# pwm-fan-controller.net
KiCad netlist of a schematic drawn in EAGLE
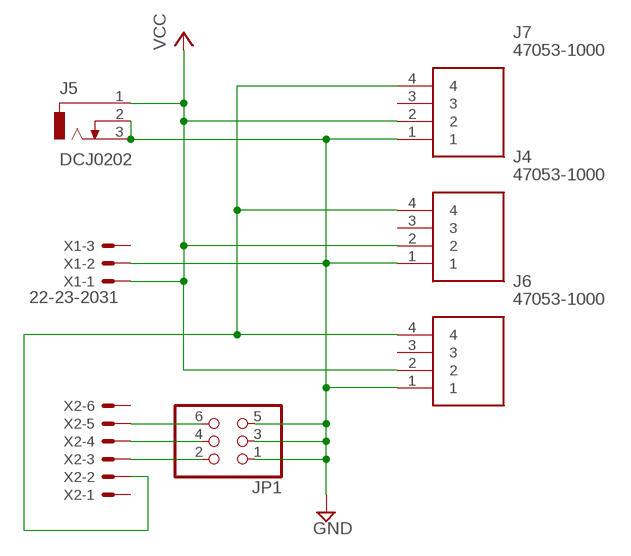
[diagram p0: schematic, sheet 1]

(export (version "E")
  (design (tool "Eeschema 10.0.6"))
  (components
    (comp (ref "J4")
      (value "47053-1000")
      (footprint "eagle-import:470531000")
      (fields (field (name "MF") "Molex"))
      (libsource (lib "eagle-import") (part "47053-1000"))
    )
    (comp (ref "J5")
      (value "DCJ0202")
      (footprint "eagle-import:DCJ0202")
      (libsource (lib "eagle-import") (part "DCJ0202"))
    )
    (comp (ref "J6")
      (value "47053-1000")
      (footprint "eagle-import:470531000")
      (fields (field (name "MF") "Molex"))
      (libsource (lib "eagle-import") (part "47053-1000"))
    )
    (comp (ref "J7")
      (value "47053-1000")
      (footprint "eagle-import:470531000")
      (fields (field (name "MF") "Molex"))
      (libsource (lib "eagle-import") (part "47053-1000"))
    )
    (comp (ref "JP1")
      (value "PINHD-2X3")
      (footprint "eagle-import:2X03")
      (libsource (lib "eagle-import") (part "PINHD-2X3"))
    )
    (comp (ref "X1")
      (value "22-23-2031")
      (footprint "eagle-import:22-23-2031")
      (fields (field (name "MF") "MOLEX"))
      (libsource (lib "eagle-import") (part "22-23-2031"))
    )
    (comp (ref "X2")
      (value "22-23-2061")
      (footprint "eagle-import:22-23-2061")
      (fields (field (name "MF") "MOLEX"))
      (libsource (lib "eagle-import") (part "22-23-2061"))
    )
  )
  (nets
    (net (code "1") (name "GND") (class "Default")
      (node (ref "J4") (pin "1") (pinfunction "1_1") (pintype "bidirectional"))
      (node (ref "J5") (pin "2") (pinfunction "2_2") (pintype "passive"))
      (node (ref "J5") (pin "3") (pinfunction "3_3") (pintype "passive"))
      (node (ref "J6") (pin "1") (pinfunction "1_1") (pintype "bidirectional"))
      (node (ref "J7") (pin "1") (pinfunction "1_1") (pintype "bidirectional"))
      (node (ref "JP1") (pin "1") (pinfunction "1_1") (pintype "passive"))
      (node (ref "JP1") (pin "3") (pinfunction "3_3") (pintype "passive"))
      (node (ref "JP1") (pin "5") (pinfunction "5_5") (pintype "passive"))
      (node (ref "X1") (pin "2") (pinfunction "S_2") (pintype "passive"))
    )
    (net (code "2") (name "Net-(X2B-S)") (class "Default")
      (node (ref "J4") (pin "4") (pinfunction "4_4") (pintype "bidirectional"))
      (node (ref "J6") (pin "4") (pinfunction "4_4") (pintype "bidirectional"))
      (node (ref "J7") (pin "4") (pinfunction "4_4") (pintype "bidirectional"))
      (node (ref "X2") (pin "2") (pinfunction "S_2") (pintype "passive"))
    )
    (net (code "3") (name "Net-(X2C-S)") (class "Default")
      (node (ref "JP1") (pin "2") (pinfunction "2_2") (pintype "passive"))
      (node (ref "X2") (pin "3") (pinfunction "S_3") (pintype "passive"))
    )
    (net (code "4") (name "Net-(X2D-S)") (class "Default")
      (node (ref "JP1") (pin "4") (pinfunction "4_4") (pintype "passive"))
      (node (ref "X2") (pin "4") (pinfunction "S_4") (pintype "passive"))
    )
    (net (code "5") (name "Net-(X2E-S)") (class "Default")
      (node (ref "JP1") (pin "6") (pinfunction "6_6") (pintype "passive"))
      (node (ref "X2") (pin "5") (pinfunction "S_5") (pintype "passive"))
    )
    (net (code "6") (name "VCC") (class "Default")
      (node (ref "J4") (pin "2") (pinfunction "2_2") (pintype "bidirectional"))
      (node (ref "J5") (pin "1") (pinfunction "1_1") (pintype "passive"))
      (node (ref "J6") (pin "2") (pinfunction "2_2") (pintype "bidirectional"))
      (node (ref "J7") (pin "2") (pinfunction "2_2") (pintype "bidirectional"))
      (node (ref "X1") (pin "1") (pinfunction "S_1") (pintype "passive"))
    )
    (net (code "7") (name "unconnected-(J4-Pad3)") (class "Default")
      (node (ref "J4") (pin "3") (pinfunction "3_3") (pintype "bidirectional"))
    )
    (net (code "8") (name "unconnected-(J6-Pad3)") (class "Default")
      (node (ref "J6") (pin "3") (pinfunction "3_3") (pintype "bidirectional"))
    )
    (net (code "9") (name "unconnected-(J7-Pad3)") (class "Default")
      (node (ref "J7") (pin "3") (pinfunction "3_3") (pintype "bidirectional"))
    )
    (net (code "10") (name "unconnected-(X1C-S-Pad3)") (class "Default")
      (node (ref "X1") (pin "3") (pinfunction "S_3") (pintype "passive"))
    )
    (net (code "11") (name "unconnected-(X2A-S-Pad1)") (class "Default")
      (node (ref "X2") (pin "1") (pinfunction "S_1") (pintype "passive"))
    )
    (net (code "12") (name "unconnected-(X2F-S-Pad6)") (class "Default")
      (node (ref "X2") (pin "6") (pinfunction "S_6") (pintype "passive"))
    )
  )
)
